# Main.net
KiCad netlist of a schematic drawn in Altium Designer
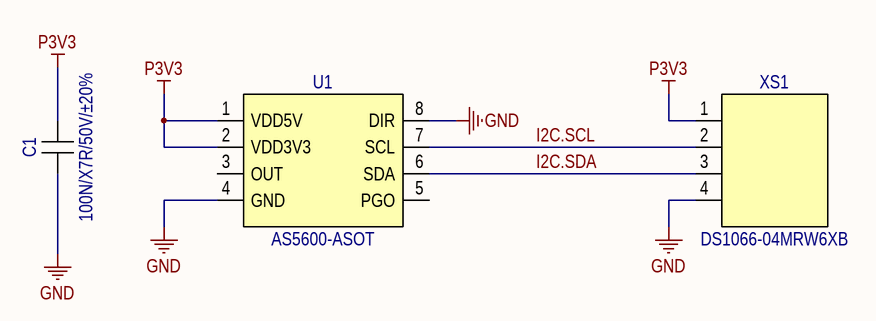
[diagram p0: Main.SchDoc]

(export (version "E")
  (design (tool "Eeschema 10.0.6"))
  (components
    (comp (ref "C1")
      (value "100N/X7R/50V/±20%")
      (footprint "Normal_Capacitor_Standard_0805-L2000-W1250-BW500-H1350")
      (description "Ceramic Capacitor SMD 0805")
      (fields
        (field (name "MANUFACTURER") "SAMSUNG ELECTRO-MECHANICS")
        (field (name "Comment") "CL21B104MBFNNNE")
      )
      (libsource (lib "Samsung-MLCC-0805") (part "CL21B104MBFNNNE"))
    )
    (comp (ref "U1")
      (value "AS5600-ASOT")
      (footprint "8-SOIC")
      (libsource (lib "mfmc_components") (part "AS5600-ASOT"))
    )
    (comp (ref "XS1")
      (value "DS1066-04MRW6XB")
      (footprint "DS1066-04MRW6XB")
      (fields (field (name "MANUFACTURER") "CONNFLY ELECTRONIC CO.,LTD."))
      (libsource (lib "mfmc_components") (part "DS1066-04MRW6XB"))
    )
  )
  (nets
    (net (code "1") (name "/I2C.SCL") (class "Default")
      (node (ref "U1") (pin "7") (pinfunction "SCL_7") (pintype "passive"))
      (node (ref "XS1") (pin "2") (pintype "passive"))
    )
    (net (code "2") (name "/I2C.SDA") (class "Default")
      (node (ref "U1") (pin "6") (pinfunction "SDA_6") (pintype "passive"))
      (node (ref "XS1") (pin "3") (pintype "passive"))
    )
    (net (code "3") (name "GND") (class "Default")
      (node (ref "C1") (pin "1") (pintype "passive"))
      (node (ref "U1") (pin "4") (pinfunction "GND_4") (pintype "passive"))
      (node (ref "U1") (pin "8") (pinfunction "DIR_8") (pintype "passive"))
      (node (ref "XS1") (pin "4") (pintype "passive"))
    )
    (net (code "4") (name "P3V3") (class "Default")
      (node (ref "C1") (pin "2") (pintype "passive"))
      (node (ref "U1") (pin "1") (pinfunction "VDD5V_1") (pintype "passive"))
      (node (ref "U1") (pin "2") (pinfunction "VDD3V3_2") (pintype "passive"))
      (node (ref "XS1") (pin "1") (pintype "passive"))
    )
    (net (code "5") (name "unconnected-(U1-OUT-Pad3)") (class "Default")
      (node (ref "U1") (pin "3") (pinfunction "OUT_3") (pintype "passive"))
    )
    (net (code "6") (name "unconnected-(U1-PGO-Pad5)") (class "Default")
      (node (ref "U1") (pin "5") (pinfunction "PGO_5") (pintype "passive"))
    )
  )
)
